# PCB_LineFollowerFullPCB.net
KiCad netlist of a schematic drawn in Altium Designer
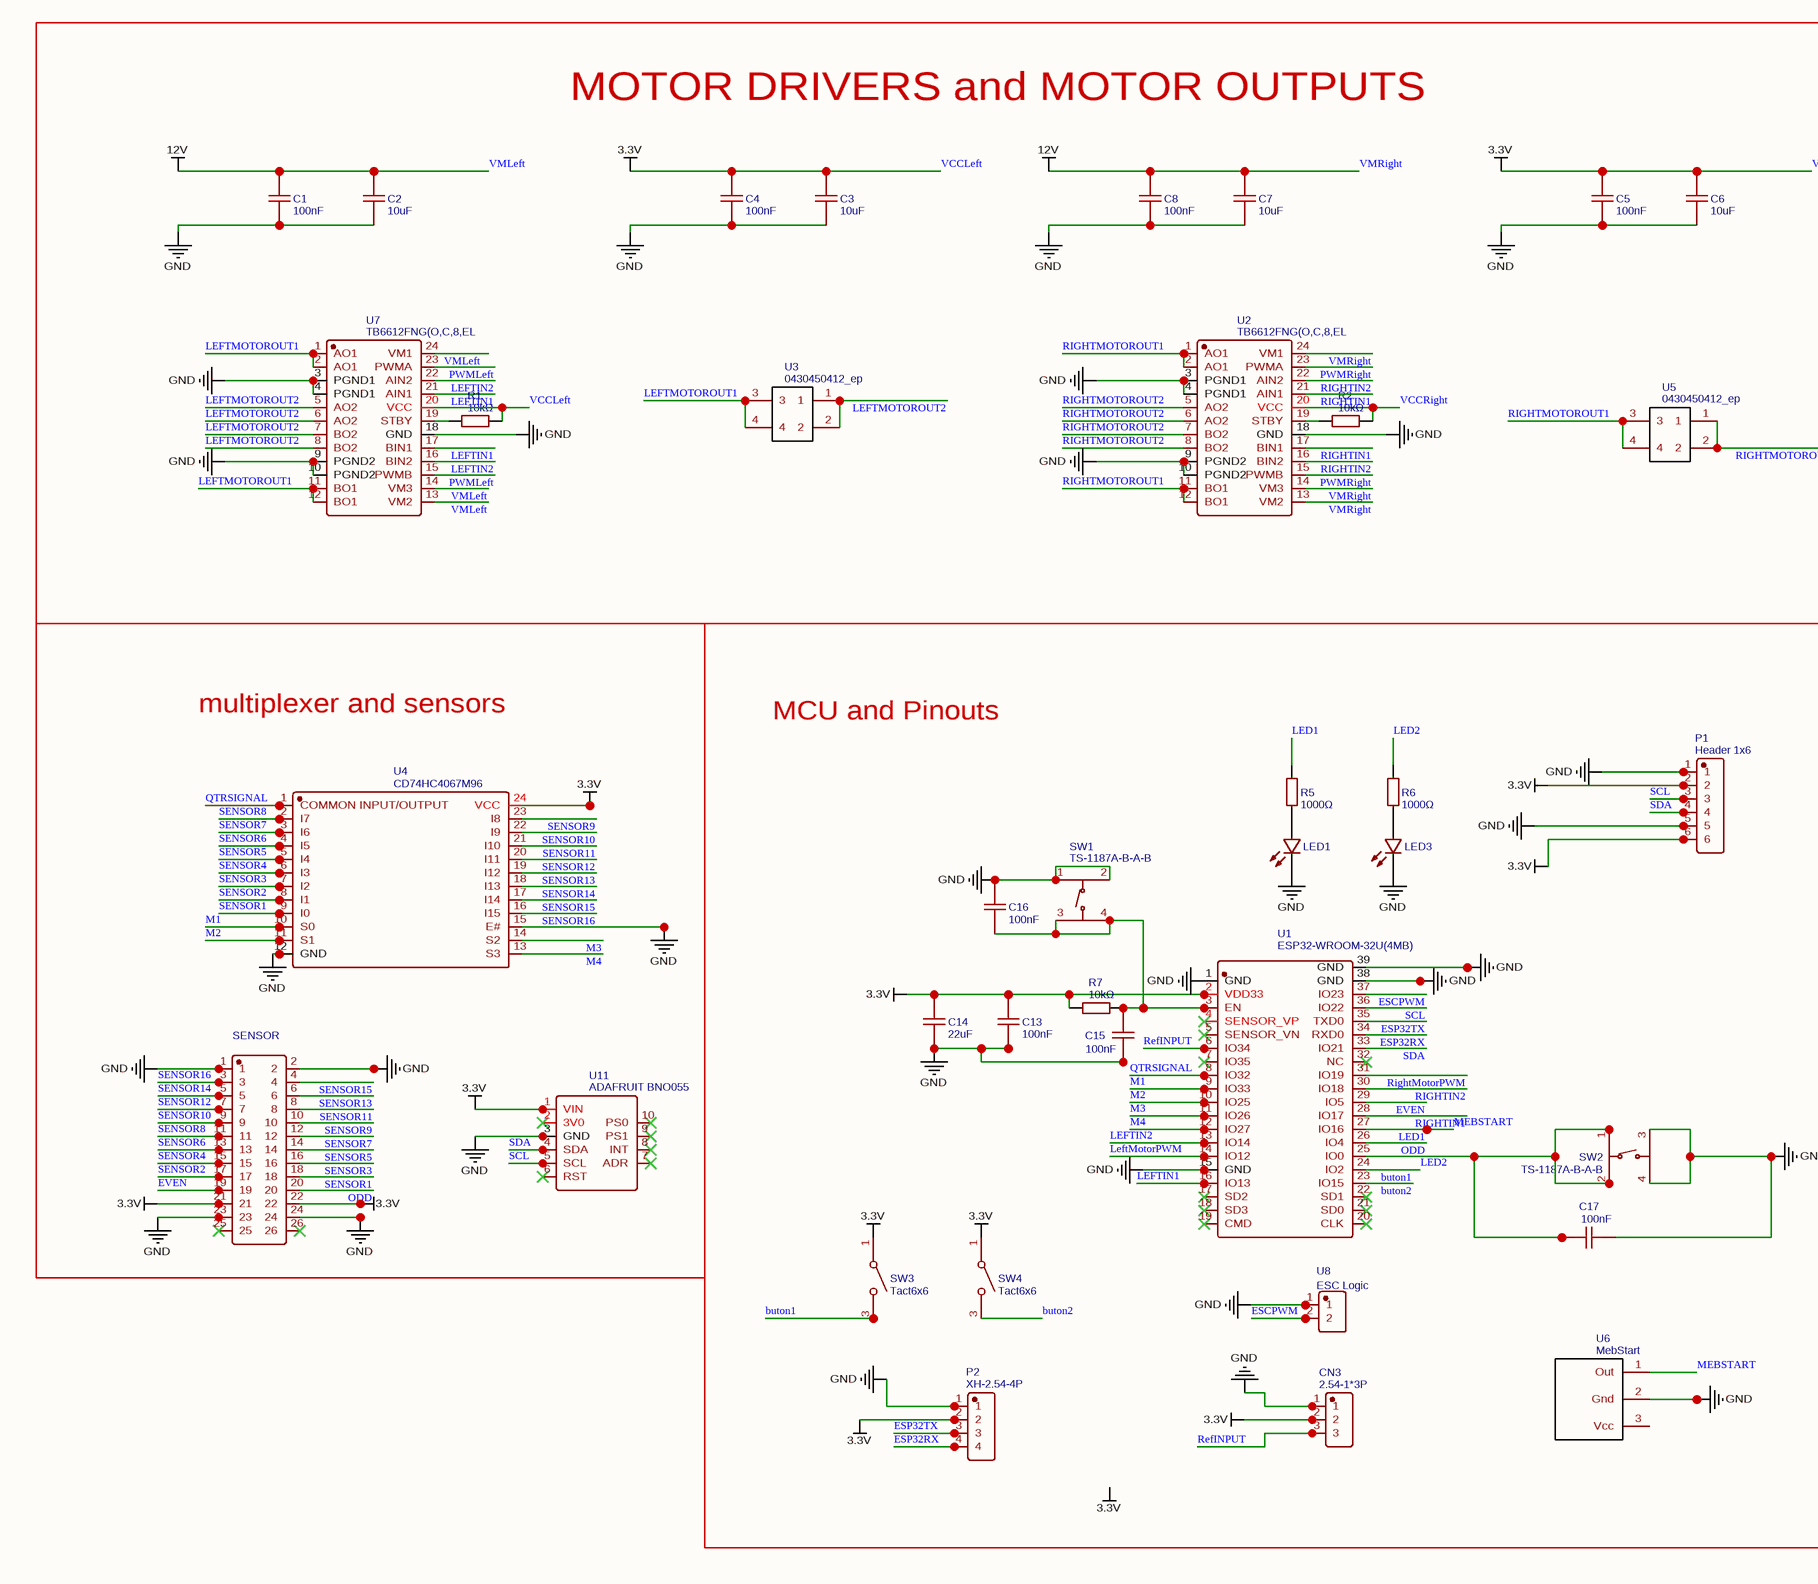
[diagram p0: PCB_LineFollowerFullPCB.schdoc, left]
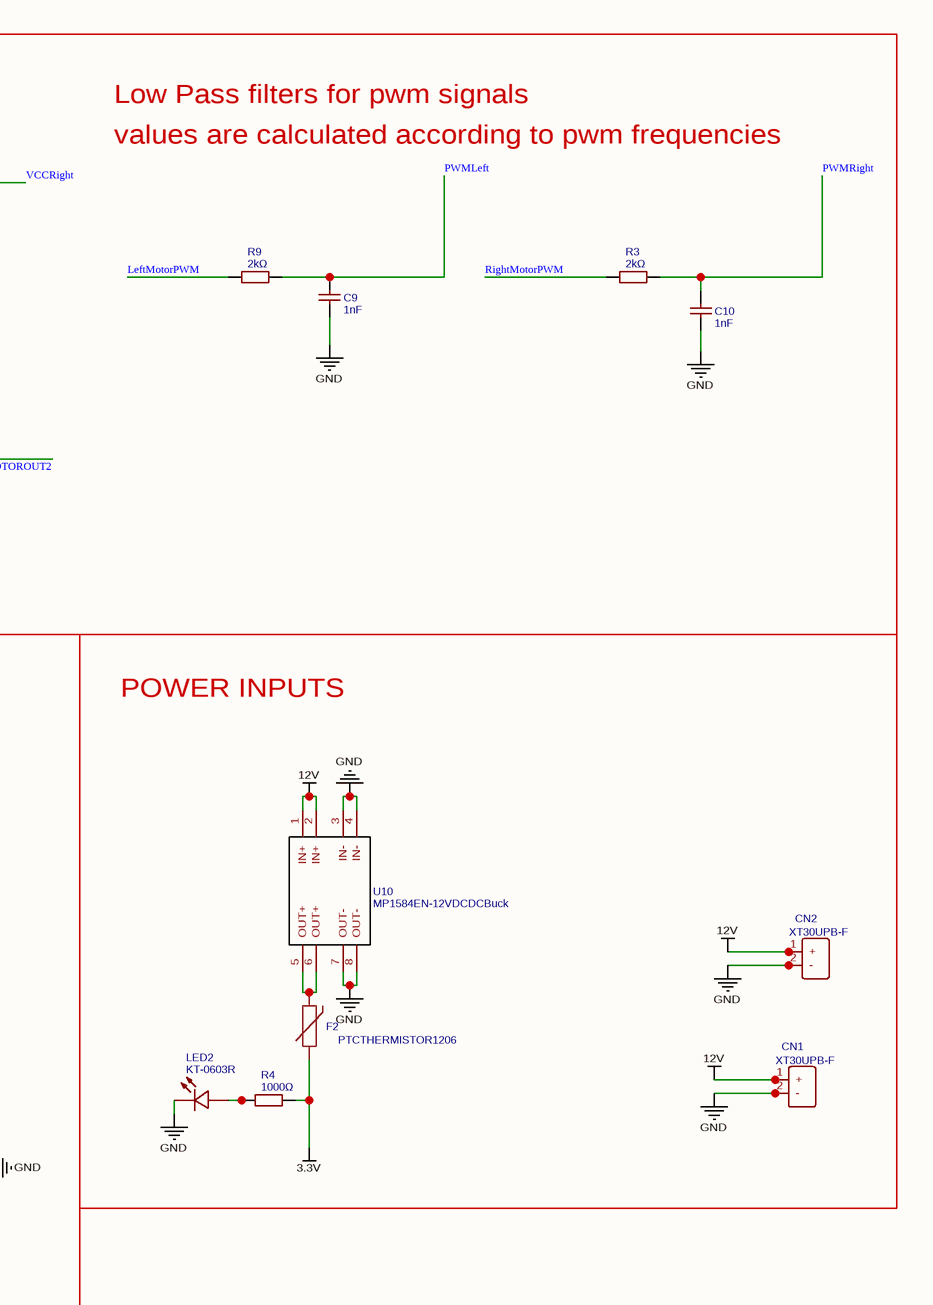
[diagram p1: PCB_LineFollowerFullPCB.schdoc, right]

(export (version "E")
  (design (tool "Eeschema 10.0.6"))
  (components
    (comp (ref "C1")
      (value "100nF")
      (fields
        (field (name "MANUFACTURER") "YAGEO(国巨)")
        (field (name "MANUFACTURER PART") "CC0603KRX7R9BB104")
      )
      (libsource (lib "altium-import") (part "root_3_100nF_"))
    )
    (comp (ref "C2")
      (value "10uF")
      (fields
        (field (name "MANUFACTURER") "SAMSUNG(三星)")
        (field (name "MANUFACTURER PART") "CL10A106MA8NRNC")
      )
      (libsource (lib "altium-import") (part "root_3_10uF_"))
    )
    (comp (ref "C3")
      (value "10uF")
      (fields
        (field (name "MANUFACTURER") "SAMSUNG(三星)")
        (field (name "MANUFACTURER PART") "CL10A106MA8NRNC")
      )
      (libsource (lib "altium-import") (part "root_3_10uF_"))
    )
    (comp (ref "C4")
      (value "100nF")
      (fields
        (field (name "MANUFACTURER") "YAGEO(国巨)")
        (field (name "MANUFACTURER PART") "CC0603KRX7R9BB104")
      )
      (libsource (lib "altium-import") (part "root_3_100nF_"))
    )
    (comp (ref "C5")
      (value "100nF")
      (fields
        (field (name "MANUFACTURER") "YAGEO(国巨)")
        (field (name "MANUFACTURER PART") "CC0603KRX7R9BB104")
      )
      (libsource (lib "altium-import") (part "root_3_100nF_"))
    )
    (comp (ref "C6")
      (value "10uF")
      (fields
        (field (name "MANUFACTURER") "SAMSUNG(三星)")
        (field (name "MANUFACTURER PART") "CL10A106MA8NRNC")
      )
      (libsource (lib "altium-import") (part "root_3_10uF_"))
    )
    (comp (ref "C7")
      (value "10uF")
      (fields
        (field (name "MANUFACTURER") "SAMSUNG(三星)")
        (field (name "MANUFACTURER PART") "CL10A106MA8NRNC")
      )
      (libsource (lib "altium-import") (part "root_3_10uF_"))
    )
    (comp (ref "C8")
      (value "100nF")
      (fields
        (field (name "MANUFACTURER") "YAGEO(国巨)")
        (field (name "MANUFACTURER PART") "CC0603KRX7R9BB104")
      )
      (libsource (lib "altium-import") (part "root_3_100nF_"))
    )
    (comp (ref "C9")
      (value "1nF")
      (fields
        (field (name "MANUFACTURER PART") "CL10B102KB8NNNC")
        (field (name "MANUFACTURER") "SAMSUNG(三星)")
      )
      (libsource (lib "altium-import") (part "root_3_1nF_"))
    )
    (comp (ref "C10")
      (value "1nF")
      (fields
        (field (name "MANUFACTURER PART") "CL10B102KB8NNNC")
        (field (name "MANUFACTURER") "SAMSUNG(三星)")
      )
      (libsource (lib "altium-import") (part "root_3_1nF_"))
    )
    (comp (ref "C13")
      (value "100nF")
      (fields
        (field (name "MANUFACTURER") "YAGEO(国巨)")
        (field (name "MANUFACTURER PART") "CC0603KRX7R9BB104")
      )
      (libsource (lib "altium-import") (part "root_3_100nF_"))
    )
    (comp (ref "C14")
      (value "22uF")
      (fields
        (field (name "MANUFACTURER") "SAMSUNG(三星)")
        (field (name "MANUFACTURER PART") "CL10A226MQ8NRNC")
      )
      (libsource (lib "altium-import") (part "root_1_22uF_"))
    )
    (comp (ref "C15")
      (value "100nF")
      (fields
        (field (name "MANUFACTURER") "YAGEO(国巨)")
        (field (name "MANUFACTURER PART") "CC0603KRX7R9BB104")
      )
      (libsource (lib "altium-import") (part "root_3_100nF_"))
    )
    (comp (ref "C16")
      (value "100nF")
      (fields
        (field (name "MANUFACTURER") "YAGEO(国巨)")
        (field (name "MANUFACTURER PART") "CC0603KRX7R9BB104")
      )
      (libsource (lib "altium-import") (part "root_3_100nF_"))
    )
    (comp (ref "C17")
      (value "100nF")
      (fields
        (field (name "MANUFACTURER") "YAGEO(国巨)")
        (field (name "MANUFACTURER PART") "CC0603KRX7R9BB104")
      )
      (libsource (lib "altium-import") (part "root_2_100nF_"))
    )
    (comp (ref "CN1")
      (value "XT30UPB-F")
      (fields
        (field (name "MANUFACTURER") "AMASS(艾迈斯)")
        (field (name "MANUFACTURER PART") "XT30UPB30-F.G.*")
        (field (name "CONTRIBUTOR") "LCSC")
      )
      (libsource (lib "altium-import") (part "root_0_XT30UPB-F_"))
    )
    (comp (ref "CN2")
      (value "XT30UPB-F")
      (fields
        (field (name "MANUFACTURER") "AMASS(艾迈斯)")
        (field (name "MANUFACTURER PART") "XT30UPB30-F.G.*")
        (field (name "CONTRIBUTOR") "LCSC")
      )
      (libsource (lib "altium-import") (part "root_0_XT30UPB-F_"))
    )
    (comp (ref "CN3")
      (value "2.54-1*3P")
      (fields (field (name "MANUFACTURER") "CAX(创都)") (field (name "CONTRIBUTOR") "LCSC"))
      (libsource (lib "altium-import") (part "root_0_2.54-1*3P_"))
    )
    (comp (ref "F2")
      (value "PTCTHERMISTOR1206")
      (description "Resettable Fuse PTC")
      (fields (field (name "CONTRIBUTOR") "varaksachin"))
      (libsource (lib "altium-import") (part "root_2_PTCTHERMISTOR1206_"))
    )
    (comp (ref "LED1")
      (value "19-217/BHC-ZL1M2RY/3T")
      (fields (field (name "MANUFACTURER") "EVERLIGHT(亿光)"))
      (libsource (lib "altium-import") (part "root_1_19-217/BHC-ZL1M2RY/3T_"))
    )
    (comp (ref "LED2")
      (value "KT-0603R")
      (fields (field (name "MANUFACTURER") "KENTO"))
      (libsource (lib "altium-import") (part "root_0_KT-0603R_"))
    )
    (comp (ref "LED3")
      (value "19-217/BHC-ZL1M2RY/3T")
      (fields (field (name "MANUFACTURER") "EVERLIGHT(亿光)"))
      (libsource (lib "altium-import") (part "root_1_19-217/BHC-ZL1M2RY/3T_"))
    )
    (comp (ref "P1")
      (value "Header 1x6")
      (fields
        (field (name "MANUFACTURER") "XFCN")
        (field (name "MANUFACTURER PART") "M3025V-1x6P")
        (field (name "CONTRIBUTOR") "erzyk")
      )
      (libsource (lib "altium-import") (part "root_0_Header 1x6_"))
    )
    (comp (ref "P2")
      (value "XH-2.54-4P")
      (fields (field (name "CONTRIBUTOR") "LCSC"))
      (libsource (lib "altium-import") (part "root_0_XH-2.54-4P_"))
    )
    (comp (ref "R1")
      (value "10kΩ")
      (fields
        (field (name "MANUFACTURER") "UNI-ROYAL(厚声)")
        (field (name "MANUFACTURER PART") "0603WAF1002T5E")
      )
      (libsource (lib "altium-import") (part "root_0_10kΩ_"))
    )
    (comp (ref "R2")
      (value "10kΩ")
      (fields
        (field (name "MANUFACTURER") "UNI-ROYAL(厚声)")
        (field (name "MANUFACTURER PART") "0603WAF1002T5E")
      )
      (libsource (lib "altium-import") (part "root_0_10kΩ_"))
    )
    (comp (ref "R3")
      (value "2kΩ")
      (fields
        (field (name "MANUFACTURER") "UNI-ROYAL(厚声)")
        (field (name "MANUFACTURER PART") "0603WAF2001T5E")
      )
      (libsource (lib "altium-import") (part "root_0_2kΩ_"))
    )
    (comp (ref "R4")
      (value "1000Ω")
      (fields
        (field (name "MANUFACTURER") "UNI-ROYAL(厚声)")
        (field (name "MANUFACTURER PART") "0603WAF1000T5E")
      )
      (libsource (lib "altium-import") (part "root_0_1000Ω_"))
    )
    (comp (ref "R5")
      (value "1000Ω")
      (fields
        (field (name "MANUFACTURER") "UNI-ROYAL(厚声)")
        (field (name "MANUFACTURER PART") "0603WAF510JT5E")
      )
      (libsource (lib "altium-import") (part "root_3_1000Ω_"))
    )
    (comp (ref "R6")
      (value "1000Ω")
      (fields
        (field (name "MANUFACTURER") "UNI-ROYAL(厚声)")
        (field (name "MANUFACTURER PART") "0603WAF510JT5E")
      )
      (libsource (lib "altium-import") (part "root_3_1000Ω_"))
    )
    (comp (ref "R7")
      (value "10kΩ")
      (fields
        (field (name "MANUFACTURER") "UNI-ROYAL(厚声)")
        (field (name "MANUFACTURER PART") "0603WAF1002T5E")
      )
      (libsource (lib "altium-import") (part "root_0_10kΩ_"))
    )
    (comp (ref "R9")
      (value "2kΩ")
      (fields
        (field (name "MANUFACTURER") "UNI-ROYAL(厚声)")
        (field (name "MANUFACTURER PART") "0603WAF2001T5E")
      )
      (libsource (lib "altium-import") (part "root_0_2kΩ_"))
    )
    (comp (ref "SENSOR")
      (value "X9555WV-2X13E-PTV01")
      (fields
        (field (name "MANUFACTURER") "XKB Connectivity(中国星坤)")
        (field (name "MANUFACTURER PART") "X9555WV-2x13E-PTV01")
        (field (name "CONTRIBUTOR") "LCSC")
      )
      (libsource (lib "altium-import") (part "root_0_X9555WV-2X13E-PTV01_"))
    )
    (comp (ref "SW1")
      (value "TS-1187A-B-A-B")
      (fields (field (name "MANUFACTURER") "XKB Connectivity(中国星坤)") (field (name "CONTRIBUTOR") "LCSC"))
      (libsource (lib "altium-import") (part "root_0_TS-1187A-B-A-B_"))
    )
    (comp (ref "SW2")
      (value "TS-1187A-B-A-B")
      (fields (field (name "MANUFACTURER") "XKB Connectivity(中国星坤)") (field (name "CONTRIBUTOR") "LCSC"))
      (libsource (lib "altium-import") (part "root_3_TS-1187A-B-A-B_"))
    )
    (comp (ref "SW3")
      (value "Tact6x6")
      (fields
        (field (name "MANUFACTURER") "BBJ")
        (field (name "MANUFACTURER PART") "Switch,6*6*6Plastic head,260G, 0.25mm,Straight line")
        (field (name "CONTRIBUTOR") "Richárd Tóth")
      )
      (libsource (lib "altium-import") (part "root_0_Tact6x6_"))
    )
    (comp (ref "SW4")
      (value "Tact6x6")
      (fields
        (field (name "MANUFACTURER") "BBJ")
        (field (name "MANUFACTURER PART") "Switch,6*6*6Plastic head,260G, 0.25mm,Straight line")
        (field (name "CONTRIBUTOR") "Richárd Tóth")
      )
      (libsource (lib "altium-import") (part "root_0_Tact6x6_"))
    )
    (comp (ref "U1")
      (value "ESP32-WROOM-32U(4MB)")
      (fields
        (field (name "MANUFACTURER") "ESPRESSIF(乐鑫)")
        (field (name "MANUFACTURER PART") "ESP32-WROOM-32U-N4")
        (field (name "CONTRIBUTOR") "LCSC")
      )
      (libsource (lib "altium-import") (part "root_0_ESP32-WROOM-32U(4MB)_"))
    )
    (comp (ref "U2")
      (value "TB6612FNG(O,C,8,EL")
      (fields (field (name "MANUFACTURER") "TOSHIBA(东芝)"))
      (libsource (lib "altium-import") (part "root_0_TB6612FNG(O,C,8,EL_"))
    )
    (comp (ref "U3")
      (value "0430450412_ep")
      (fields (field (name "CONTRIBUTOR") "epsilor"))
      (libsource (lib "altium-import") (part "root_0_0430450412_ep_"))
    )
    (comp (ref "U4")
      (value "CD74HC4067M96")
      (fields (field (name "MANUFACTURER") "TI(德州仪器)") (field (name "CONTRIBUTOR") "LCSC"))
      (libsource (lib "altium-import") (part "root_0_CD74HC4067M96_"))
    )
    (comp (ref "U5")
      (value "0430450412_ep")
      (fields (field (name "CONTRIBUTOR") "epsilor"))
      (libsource (lib "altium-import") (part "root_0_0430450412_ep_"))
    )
    (comp (ref "U6")
      (value "MebStart")
      (fields (field (name "CONTRIBUTOR") "cikkan"))
      (libsource (lib "altium-import") (part "root_0_MebStart_"))
    )
    (comp (ref "U7")
      (value "TB6612FNG(O,C,8,EL")
      (fields (field (name "MANUFACTURER") "TOSHIBA(东芝)"))
      (libsource (lib "altium-import") (part "root_0_TB6612FNG(O,C,8,EL_"))
    )
    (comp (ref "U8")
      (value "ESC Logic")
      (fields (field (name "MANUFACTURER PART") "XH-2P-2.54") (field (name "CONTRIBUTOR") "LCSC"))
      (libsource (lib "altium-import") (part "root_0_ESC Logic_"))
    )
    (comp (ref "U10")
      (value "MP1584EN-12VDCDCBuck")
      (fields
        (field (name "MANUFACTURER") "eBoot")
        (field (name "MANUFACTURER PART") "MP1584EN")
        (field (name "CONTRIBUTOR") "pep9571")
      )
      (libsource (lib "altium-import") (part "root_0_MP1584EN-12VDCDCBuck_"))
    )
    (comp (ref "U11")
      (value "ADAFRUIT BNO055")
      (fields (field (name "CONTRIBUTOR") "andreastryph"))
      (libsource (lib "altium-import") (part "root_0_ADAFRUIT BNO055_"))
    )
  )
  (nets
    (net (code "1") (name "/ESCPWM") (class "Default")
      (node (ref "U1") (pin "37") (pinfunction "IO23_37") (pintype "passive"))
      (node (ref "U8") (pin "2") (pinfunction "2_2") (pintype "passive"))
    )
    (net (code "2") (name "/ESP32RX") (class "Default")
      (node (ref "P2") (pin "4") (pinfunction "4_4") (pintype "passive"))
      (node (ref "U1") (pin "34") (pinfunction "RXD0_34") (pintype "passive"))
    )
    (net (code "3") (name "/ESP32TX") (class "Default")
      (node (ref "P2") (pin "3") (pinfunction "3_3") (pintype "passive"))
      (node (ref "U1") (pin "35") (pinfunction "TXD0_35") (pintype "passive"))
    )
    (net (code "4") (name "/EVEN") (class "Default")
      (node (ref "SENSOR") (pin "19") (pinfunction "19_19") (pintype "passive"))
      (node (ref "U1") (pin "29") (pinfunction "IO5_29") (pintype "passive"))
    )
    (net (code "5") (name "/LED1") (class "Default")
      (node (ref "R5") (pin "1") (pinfunction "1_1") (pintype "passive"))
      (node (ref "U1") (pin "27") (pinfunction "IO16_27") (pintype "passive"))
      (node (ref "U6") (pin "1") (pinfunction "Out_1") (pintype "passive"))
    )
    (net (code "6") (name "/LED2") (class "Default")
      (node (ref "R6") (pin "1") (pinfunction "1_1") (pintype "passive"))
      (node (ref "SW3") (pin "3") (pinfunction "2_3") (pintype "passive"))
      (node (ref "U1") (pin "24") (pinfunction "IO2_24") (pintype "passive"))
    )
    (net (code "7") (name "/LEFTIN1") (class "Default")
      (node (ref "U1") (pin "16") (pinfunction "IO13_16") (pintype "passive"))
      (node (ref "U7") (pin "17") (pinfunction "BIN1_17") (pintype "passive"))
      (node (ref "U7") (pin "21") (pinfunction "AIN1_21") (pintype "passive"))
    )
    (net (code "8") (name "/LEFTIN2") (class "Default")
      (node (ref "U1") (pin "13") (pinfunction "IO14_13") (pintype "passive"))
      (node (ref "U7") (pin "16") (pinfunction "BIN2_16") (pintype "passive"))
      (node (ref "U7") (pin "22") (pinfunction "AIN2_22") (pintype "passive"))
    )
    (net (code "9") (name "/LEFTMOTOROUT1") (class "Default")
      (node (ref "U3") (pin "3") (pinfunction "3_3") (pintype "passive"))
      (node (ref "U3") (pin "4") (pinfunction "4_4") (pintype "passive"))
      (node (ref "U7") (pin "1") (pinfunction "AO1_1") (pintype "passive"))
      (node (ref "U7") (pin "11") (pinfunction "BO1_11") (pintype "passive"))
      (node (ref "U7") (pin "12") (pinfunction "BO1_12") (pintype "passive"))
      (node (ref "U7") (pin "2") (pinfunction "AO1_2") (pintype "passive"))
    )
    (net (code "10") (name "/LEFTMOTOROUT2") (class "Default")
      (node (ref "U3") (pin "1") (pinfunction "1_1") (pintype "passive"))
      (node (ref "U3") (pin "2") (pinfunction "2_2") (pintype "passive"))
      (node (ref "U7") (pin "5") (pinfunction "AO2_5") (pintype "passive"))
      (node (ref "U7") (pin "6") (pinfunction "AO2_6") (pintype "passive"))
      (node (ref "U7") (pin "7") (pinfunction "BO2_7") (pintype "passive"))
      (node (ref "U7") (pin "8") (pinfunction "BO2_8") (pintype "passive"))
    )
    (net (code "11") (name "/LeftMotorPWM") (class "Default")
      (node (ref "R9") (pin "1") (pinfunction "1_1") (pintype "passive"))
      (node (ref "U1") (pin "14") (pinfunction "IO12_14") (pintype "passive"))
    )
    (net (code "12") (name "/M1") (class "Default")
      (node (ref "U1") (pin "9") (pinfunction "IO33_9") (pintype "passive"))
      (node (ref "U4") (pin "10") (pinfunction "S0_10") (pintype "passive"))
    )
    (net (code "13") (name "/M2") (class "Default")
      (node (ref "U1") (pin "10") (pinfunction "IO25_10") (pintype "passive"))
      (node (ref "U4") (pin "11") (pinfunction "S1_11") (pintype "passive"))
    )
    (net (code "14") (name "/M3") (class "Default")
      (node (ref "U1") (pin "11") (pinfunction "IO26_11") (pintype "passive"))
      (node (ref "U4") (pin "14") (pinfunction "S2_14") (pintype "passive"))
    )
    (net (code "15") (name "/M4") (class "Default")
      (node (ref "U1") (pin "12") (pinfunction "IO27_12") (pintype "passive"))
      (node (ref "U4") (pin "13") (pinfunction "S3_13") (pintype "passive"))
    )
    (net (code "16") (name "/ODD") (class "Default")
      (node (ref "SENSOR") (pin "20") (pinfunction "20_20") (pintype "passive"))
      (node (ref "U1") (pin "26") (pinfunction "IO4_26") (pintype "passive"))
    )
    (net (code "17") (name "/PWMLeft") (class "Default")
      (node (ref "C9") (pin "1") (pinfunction "1_1") (pintype "passive"))
      (node (ref "R9") (pin "2") (pinfunction "2_2") (pintype "passive"))
      (node (ref "U7") (pin "15") (pinfunction "PWMB_15") (pintype "passive"))
      (node (ref "U7") (pin "23") (pinfunction "PWMA_23") (pintype "passive"))
    )
    (net (code "18") (name "/PWMRight") (class "Default")
      (node (ref "C10") (pin "1") (pinfunction "1_1") (pintype "passive"))
      (node (ref "R3") (pin "2") (pinfunction "2_2") (pintype "passive"))
      (node (ref "U2") (pin "15") (pinfunction "PWMB_15") (pintype "passive"))
      (node (ref "U2") (pin "23") (pinfunction "PWMA_23") (pintype "passive"))
    )
    (net (code "19") (name "/QTRSIGNAL") (class "Default")
      (node (ref "U1") (pin "8") (pinfunction "IO32_8") (pintype "passive"))
      (node (ref "U4") (pin "1") (pinfunction "COMMON_INPUT/OUTPUT_1") (pintype "passive"))
    )
    (net (code "20") (name "/RIGHTIN1") (class "Default")
      (node (ref "U1") (pin "28") (pinfunction "IO17_28") (pintype "passive"))
      (node (ref "U2") (pin "17") (pinfunction "BIN1_17") (pintype "passive"))
      (node (ref "U2") (pin "21") (pinfunction "AIN1_21") (pintype "passive"))
    )
    (net (code "21") (name "/RIGHTIN2") (class "Default")
      (node (ref "U1") (pin "30") (pinfunction "IO18_30") (pintype "passive"))
      (node (ref "U2") (pin "16") (pinfunction "BIN2_16") (pintype "passive"))
      (node (ref "U2") (pin "22") (pinfunction "AIN2_22") (pintype "passive"))
    )
    (net (code "22") (name "/RIGHTMOTOROUT1") (class "Default")
      (node (ref "U2") (pin "1") (pinfunction "AO1_1") (pintype "passive"))
      (node (ref "U2") (pin "11") (pinfunction "BO1_11") (pintype "passive"))
      (node (ref "U2") (pin "12") (pinfunction "BO1_12") (pintype "passive"))
      (node (ref "U2") (pin "2") (pinfunction "AO1_2") (pintype "passive"))
      (node (ref "U5") (pin "3") (pinfunction "3_3") (pintype "passive"))
      (node (ref "U5") (pin "4") (pinfunction "4_4") (pintype "passive"))
    )
    (net (code "23") (name "/RIGHTMOTOROUT2") (class "Default")
      (node (ref "U2") (pin "5") (pinfunction "AO2_5") (pintype "passive"))
      (node (ref "U2") (pin "6") (pinfunction "AO2_6") (pintype "passive"))
      (node (ref "U2") (pin "7") (pinfunction "BO2_7") (pintype "passive"))
      (node (ref "U2") (pin "8") (pinfunction "BO2_8") (pintype "passive"))
      (node (ref "U5") (pin "1") (pinfunction "1_1") (pintype "passive"))
      (node (ref "U5") (pin "2") (pinfunction "2_2") (pintype "passive"))
    )
    (net (code "24") (name "/RefINPUT") (class "Default")
      (node (ref "CN3") (pin "3") (pinfunction "3_3") (pintype "passive"))
      (node (ref "U1") (pin "6") (pinfunction "IO34_6") (pintype "passive"))
    )
    (net (code "25") (name "/RightMotorPWM") (class "Default")
      (node (ref "R3") (pin "1") (pinfunction "1_1") (pintype "passive"))
      (node (ref "U1") (pin "31") (pinfunction "IO19_31") (pintype "passive"))
    )
    (net (code "26") (name "/SCL") (class "Default")
      (node (ref "P1") (pin "3") (pinfunction "3_3") (pintype "passive"))
      (node (ref "U1") (pin "36") (pinfunction "IO22_36") (pintype "passive"))
      (node (ref "U11") (pin "5") (pinfunction "SCL_5") (pintype "passive"))
    )
    (net (code "27") (name "/SDA") (class "Default")
      (node (ref "P1") (pin "4") (pinfunction "4_4") (pintype "passive"))
      (node (ref "U1") (pin "33") (pinfunction "IO21_33") (pintype "passive"))
      (node (ref "U11") (pin "4") (pinfunction "SDA_4") (pintype "passive"))
    )
    (net (code "28") (name "/SENSOR1") (class "Default")
      (node (ref "SENSOR") (pin "18") (pinfunction "18_18") (pintype "passive"))
      (node (ref "U4") (pin "9") (pinfunction "I0_9") (pintype "passive"))
    )
    (net (code "29") (name "/SENSOR2") (class "Default")
      (node (ref "SENSOR") (pin "17") (pinfunction "17_17") (pintype "passive"))
      (node (ref "U4") (pin "8") (pinfunction "I1_8") (pintype "passive"))
    )
    (net (code "30") (name "/SENSOR3") (class "Default")
      (node (ref "SENSOR") (pin "16") (pinfunction "16_16") (pintype "passive"))
      (node (ref "U4") (pin "7") (pinfunction "I2_7") (pintype "passive"))
    )
    (net (code "31") (name "/SENSOR4") (class "Default")
      (node (ref "SENSOR") (pin "15") (pinfunction "15_15") (pintype "passive"))
      (node (ref "U4") (pin "6") (pinfunction "I3_6") (pintype "passive"))
    )
    (net (code "32") (name "/SENSOR5") (class "Default")
      (node (ref "SENSOR") (pin "14") (pinfunction "14_14") (pintype "passive"))
      (node (ref "U4") (pin "5") (pinfunction "I4_5") (pintype "passive"))
    )
    (net (code "33") (name "/SENSOR6") (class "Default")
      (node (ref "SENSOR") (pin "13") (pinfunction "13_13") (pintype "passive"))
      (node (ref "U4") (pin "4") (pinfunction "I5_4") (pintype "passive"))
    )
    (net (code "34") (name "/SENSOR7") (class "Default")
      (node (ref "SENSOR") (pin "12") (pinfunction "12_12") (pintype "passive"))
      (node (ref "U4") (pin "3") (pinfunction "I6_3") (pintype "passive"))
    )
    (net (code "35") (name "/SENSOR8") (class "Default")
      (node (ref "SENSOR") (pin "11") (pinfunction "11_11") (pintype "passive"))
      (node (ref "U4") (pin "2") (pinfunction "I7_2") (pintype "passive"))
    )
    (net (code "36") (name "/SENSOR9") (class "Default")
      (node (ref "SENSOR") (pin "10") (pinfunction "10_10") (pintype "passive"))
      (node (ref "U4") (pin "23") (pinfunction "I8_23") (pintype "passive"))
    )
    (net (code "37") (name "/SENSOR10") (class "Default")
      (node (ref "SENSOR") (pin "9") (pinfunction "9_9") (pintype "passive"))
      (node (ref "U4") (pin "22") (pinfunction "I9_22") (pintype "passive"))
    )
    (net (code "38") (name "/SENSOR11") (class "Default")
      (node (ref "SENSOR") (pin "8") (pinfunction "8_8") (pintype "passive"))
      (node (ref "U4") (pin "21") (pinfunction "I10_21") (pintype "passive"))
    )
    (net (code "39") (name "/SENSOR12") (class "Default")
      (node (ref "SENSOR") (pin "7") (pinfunction "7_7") (pintype "passive"))
      (node (ref "U4") (pin "20") (pinfunction "I11_20") (pintype "passive"))
    )
    (net (code "40") (name "/SENSOR13") (class "Default")
      (node (ref "SENSOR") (pin "6") (pinfunction "6_6") (pintype "passive"))
      (node (ref "U4") (pin "19") (pinfunction "I12_19") (pintype "passive"))
    )
    (net (code "41") (name "/SENSOR14") (class "Default")
      (node (ref "SENSOR") (pin "5") (pinfunction "5_5") (pintype "passive"))
      (node (ref "U4") (pin "18") (pinfunction "I13_18") (pintype "passive"))
    )
    (net (code "42") (name "/SENSOR15") (class "Default")
      (node (ref "SENSOR") (pin "4") (pinfunction "4_4") (pintype "passive"))
      (node (ref "U4") (pin "17") (pinfunction "I14_17") (pintype "passive"))
    )
    (net (code "43") (name "/SENSOR16") (class "Default")
      (node (ref "SENSOR") (pin "3") (pinfunction "3_3") (pintype "passive"))
      (node (ref "U4") (pin "16") (pinfunction "I15_16") (pintype "passive"))
    )
    (net (code "44") (name "/buton2") (class "Default")
      (node (ref "SW4") (pin "3") (pinfunction "2_3") (pintype "passive"))
      (node (ref "U1") (pin "23") (pinfunction "IO15_23") (pintype "passive"))
    )
    (net (code "45") (name "3.3V") (class "Default")
      (node (ref "C13") (pin "1") (pinfunction "1_1") (pintype "passive"))
      (node (ref "C14") (pin "2") (pinfunction "2_2") (pintype "passive"))
      (node (ref "C3") (pin "1") (pinfunction "1_1") (pintype "passive"))
      (node (ref "C4") (pin "1") (pinfunction "1_1") (pintype "passive"))
      (node (ref "C5") (pin "1") (pinfunction "1_1") (pintype "passive"))
      (node (ref "C6") (pin "1") (pinfunction "1_1") (pintype "passive"))
      (node (ref "CN3") (pin "2") (pinfunction "2_2") (pintype "passive"))
      (node (ref "F2") (pin "1") (pinfunction "1_1") (pintype "passive"))
      (node (ref "P1") (pin "2") (pinfunction "2_2") (pintype "passive"))
      (node (ref "P1") (pin "6") (pinfunction "6_6") (pintype "passive"))
      (node (ref "P2") (pin "2") (pinfunction "2_2") (pintype "passive"))
      (node (ref "R1") (pin "2") (pinfunction "2_2") (pintype "passive"))
      (node (ref "R2") (pin "2") (pinfunction "2_2") (pintype "passive"))
      (node (ref "R4") (pin "2") (pinfunction "2_2") (pintype "passive"))
      (node (ref "R7") (pin "1") (pinfunction "1_1") (pintype "passive"))
      (node (ref "SENSOR") (pin "21") (pinfunction "21_21") (pintype "passive"))
      (node (ref "SENSOR") (pin "22") (pinfunction "22_22") (pintype "passive"))
      (node (ref "SW3") (pin "1") (pinfunction "1_1") (pintype "passive"))
      (node (ref "SW4") (pin "1") (pinfunction "1_1") (pintype "passive"))
      (node (ref "U1") (pin "2") (pinfunction "VDD33_2") (pintype "passive"))
      (node (ref "U11") (pin "1") (pinfunction "VIN_1") (pintype "passive"))
      (node (ref "U2") (pin "20") (pinfunction "VCC_20") (pintype "passive"))
      (node (ref "U4") (pin "24") (pinfunction "VCC_24") (pintype "passive"))
      (node (ref "U7") (pin "20") (pinfunction "VCC_20") (pintype "passive"))
    )
    (net (code "46") (name "12V") (class "Default")
      (node (ref "C1") (pin "1") (pinfunction "1_1") (pintype "passive"))
      (node (ref "C2") (pin "1") (pinfunction "1_1") (pintype "passive"))
      (node (ref "C7") (pin "1") (pinfunction "1_1") (pintype "passive"))
      (node (ref "C8") (pin "1") (pinfunction "1_1") (pintype "passive"))
      (node (ref "CN1") (pin "1") (pinfunction "+_1") (pintype "passive"))
      (node (ref "CN2") (pin "1") (pinfunction "+_1") (pintype "passive"))
      (node (ref "U10") (pin "1") (pinfunction "IN+_1") (pintype "passive"))
      (node (ref "U10") (pin "2") (pinfunction "IN+_2") (pintype "passive"))
      (node (ref "U2") (pin "13") (pinfunction "VM2_13") (pintype "passive"))
      (node (ref "U2") (pin "14") (pinfunction "VM3_14") (pintype "passive"))
      (node (ref "U2") (pin "24") (pinfunction "VM1_24") (pintype "passive"))
      (node (ref "U7") (pin "13") (pinfunction "VM2_13") (pintype "passive"))
      (node (ref "U7") (pin "14") (pinfunction "VM3_14") (pintype "passive"))
      (node (ref "U7") (pin "24") (pinfunction "VM1_24") (pintype "passive"))
    )
    (net (code "47") (name "GND") (class "Default")
      (node (ref "C1") (pin "2") (pinfunction "2_2") (pintype "passive"))
      (node (ref "C10") (pin "2") (pinfunction "2_2") (pintype "passive"))
      (node (ref "C13") (pin "2") (pinfunction "2_2") (pintype "passive"))
      (node (ref "C14") (pin "1") (pinfunction "1_1") (pintype "passive"))
      (node (ref "C15") (pin "2") (pinfunction "2_2") (pintype "passive"))
      (node (ref "C16") (pin "1") (pinfunction "1_1") (pintype "passive"))
      (node (ref "C17") (pin "2") (pinfunction "2_2") (pintype "passive"))
      (node (ref "C2") (pin "2") (pinfunction "2_2") (pintype "passive"))
      (node (ref "C3") (pin "2") (pinfunction "2_2") (pintype "passive"))
      (node (ref "C4") (pin "2") (pinfunction "2_2") (pintype "passive"))
      (node (ref "C5") (pin "2") (pinfunction "2_2") (pintype "passive"))
      (node (ref "C6") (pin "2") (pinfunction "2_2") (pintype "passive"))
      (node (ref "C7") (pin "2") (pinfunction "2_2") (pintype "passive"))
      (node (ref "C8") (pin "2") (pinfunction "2_2") (pintype "passive"))
      (node (ref "C9") (pin "2") (pinfunction "2_2") (pintype "passive"))
      (node (ref "CN1") (pin "2") (pinfunction "-_2") (pintype "passive"))
      (node (ref "CN2") (pin "2") (pinfunction "-_2") (pintype "passive"))
      (node (ref "CN3") (pin "1") (pinfunction "1_1") (pintype "passive"))
      (node (ref "LED1") (pin "1") (pinfunction "C_1") (pintype "passive"))
      (node (ref "LED2") (pin "1") (pinfunction "K_1") (pintype "passive"))
      (node (ref "LED3") (pin "1") (pinfunction "C_1") (pintype "passive"))
      (node (ref "P1") (pin "1") (pinfunction "1_1") (pintype "passive"))
      (node (ref "P1") (pin "5") (pinfunction "5_5") (pintype "passive"))
      (node (ref "P2") (pin "1") (pinfunction "1_1") (pintype "passive"))
      (node (ref "SENSOR") (pin "1") (pinfunction "1_1") (pintype "passive"))
      (node (ref "SENSOR") (pin "2") (pinfunction "2_2") (pintype "passive"))
      (node (ref "SENSOR") (pin "23") (pinfunction "23_23") (pintype "passive"))
      (node (ref "SENSOR") (pin "24") (pinfunction "24_24") (pintype "passive"))
      (node (ref "SW1") (pin "1") (pinfunction "A_1") (pintype "passive"))
      (node (ref "SW1") (pin "2") (pinfunction "B_2") (pintype "passive"))
      (node (ref "SW2") (pin "3") (pinfunction "C_3") (pintype "passive"))
      (node (ref "SW2") (pin "4") (pinfunction "D_4") (pintype "passive"))
      (node (ref "U1") (pin "1") (pinfunction "GND_1") (pintype "passive"))
      (node (ref "U1") (pin "15") (pinfunction "GND_15") (pintype "passive"))
      (node (ref "U1") (pin "38") (pinfunction "GND_38") (pintype "passive"))
      (node (ref "U1") (pin "39") (pinfunction "GND_39") (pintype "passive"))
      (node (ref "U10") (pin "3") (pinfunction "IN-_3") (pintype "passive"))
      (node (ref "U10") (pin "4") (pinfunction "IN-_4") (pintype "passive"))
      (node (ref "U10") (pin "7") (pinfunction "OUT-_7") (pintype "passive"))
      (node (ref "U10") (pin "8") (pinfunction "OUT-_8") (pintype "passive"))
      (node (ref "U11") (pin "3") (pinfunction "GND_3") (pintype "passive"))
      (node (ref "U2") (pin "10") (pinfunction "PGND2_10") (pintype "passive"))
      (node (ref "U2") (pin "18") (pinfunction "GND_18") (pintype "passive"))
      (node (ref "U2") (pin "3") (pinfunction "PGND1_3") (pintype "passive"))
      (node (ref "U2") (pin "4") (pinfunction "PGND1_4") (pintype "passive"))
      (node (ref "U2") (pin "9") (pinfunction "PGND2_9") (pintype "passive"))
      (node (ref "U4") (pin "12") (pinfunction "GND_12") (pintype "passive"))
      (node (ref "U4") (pin "15") (pinfunction "E#_15") (pintype "passive"))
      (node (ref "U6") (pin "2") (pinfunction "Gnd_2") (pintype "passive"))
      (node (ref "U7") (pin "10") (pinfunction "PGND2_10") (pintype "passive"))
      (node (ref "U7") (pin "18") (pinfunction "GND_18") (pintype "passive"))
      (node (ref "U7") (pin "3") (pinfunction "PGND1_3") (pintype "passive"))
      (node (ref "U7") (pin "4") (pinfunction "PGND1_4") (pintype "passive"))
      (node (ref "U7") (pin "9") (pinfunction "PGND2_9") (pintype "passive"))
      (node (ref "U8") (pin "1") (pinfunction "1_1") (pintype "passive"))
    )
    (net (code "48") (name "Net-(F2-Pad2)") (class "Default")
      (node (ref "F2") (pin "2") (pinfunction "2_2") (pintype "passive"))
      (node (ref "U10") (pin "5") (pinfunction "OUT+_5") (pintype "passive"))
      (node (ref "U10") (pin "6") (pinfunction "OUT+_6") (pintype "passive"))
    )
    (net (code "49") (name "Net-(LED1-A)") (class "Default")
      (node (ref "LED1") (pin "2") (pinfunction "A_2") (pintype "passive"))
      (node (ref "R5") (pin "2") (pinfunction "2_2") (pintype "passive"))
    )
    (net (code "50") (name "Net-(LED2-A)") (class "Default")
      (node (ref "LED2") (pin "2") (pinfunction "A_2") (pintype "passive"))
      (node (ref "R4") (pin "1") (pinfunction "1_1") (pintype "passive"))
    )
    (net (code "51") (name "Net-(LED3-A)") (class "Default")
      (node (ref "LED3") (pin "2") (pinfunction "A_2") (pintype "passive"))
      (node (ref "R6") (pin "2") (pinfunction "2_2") (pintype "passive"))
    )
    (net (code "52") (name "Net-(SW1-C)") (class "Default")
      (node (ref "C15") (pin "1") (pinfunction "1_1") (pintype "passive"))
      (node (ref "C16") (pin "2") (pinfunction "2_2") (pintype "passive"))
      (node (ref "R7") (pin "2") (pinfunction "2_2") (pintype "passive"))
      (node (ref "SW1") (pin "3") (pinfunction "C_3") (pintype "passive"))
      (node (ref "SW1") (pin "4") (pinfunction "D_4") (pintype "passive"))
      (node (ref "U1") (pin "3") (pinfunction "EN_3") (pintype "passive"))
    )
    (net (code "53") (name "Net-(SW2-A)") (class "Default")
      (node (ref "C17") (pin "1") (pinfunction "1_1") (pintype "passive"))
      (node (ref "SW2") (pin "1") (pinfunction "A_1") (pintype "passive"))
      (node (ref "SW2") (pin "2") (pinfunction "B_2") (pintype "passive"))
      (node (ref "U1") (pin "25") (pinfunction "IO0_25") (pintype "passive"))
    )
    (net (code "54") (name "Net-(U2-STBY)") (class "Default")
      (node (ref "R2") (pin "1") (pinfunction "1_1") (pintype "passive"))
      (node (ref "U2") (pin "19") (pinfunction "STBY_19") (pintype "passive"))
    )
    (net (code "55") (name "Net-(U7-STBY)") (class "Default")
      (node (ref "R1") (pin "1") (pinfunction "1_1") (pintype "passive"))
      (node (ref "U7") (pin "19") (pinfunction "STBY_19") (pintype "passive"))
    )
    (net (code "56") (name "unconnected-(SENSOR-Pad25)") (class "Default")
      (node (ref "SENSOR") (pin "25") (pinfunction "25_25") (pintype "passive+no_connect"))
    )
    (net (code "57") (name "unconnected-(SENSOR-Pad26)") (class "Default")
      (node (ref "SENSOR") (pin "26") (pinfunction "26_26") (pintype "passive+no_connect"))
    )
    (net (code "58") (name "unconnected-(U1-CLK-Pad20)") (class "Default")
      (node (ref "U1") (pin "20") (pinfunction "CLK_20") (pintype "passive+no_connect"))
    )
    (net (code "59") (name "unconnected-(U1-CMD-Pad19)") (class "Default")
      (node (ref "U1") (pin "19") (pinfunction "CMD_19") (pintype "passive+no_connect"))
    )
    (net (code "60") (name "unconnected-(U1-IO35-Pad7)") (class "Default")
      (node (ref "U1") (pin "7") (pinfunction "IO35_7") (pintype "passive+no_connect"))
    )
    (net (code "61") (name "unconnected-(U1-NC-Pad32)") (class "Default")
      (node (ref "U1") (pin "32") (pinfunction "NC_32") (pintype "passive+no_connect"))
    )
    (net (code "62") (name "unconnected-(U1-SD0-Pad21)") (class "Default")
      (node (ref "U1") (pin "21") (pinfunction "SD0_21") (pintype "passive+no_connect"))
    )
    (net (code "63") (name "unconnected-(U1-SD1-Pad22)") (class "Default")
      (node (ref "U1") (pin "22") (pinfunction "SD1_22") (pintype "passive+no_connect"))
    )
    (net (code "64") (name "unconnected-(U1-SD2-Pad17)") (class "Default")
      (node (ref "U1") (pin "17") (pinfunction "SD2_17") (pintype "passive+no_connect"))
    )
    (net (code "65") (name "unconnected-(U1-SD3-Pad18)") (class "Default")
      (node (ref "U1") (pin "18") (pinfunction "SD3_18") (pintype "passive+no_connect"))
    )
    (net (code "66") (name "unconnected-(U1-SENSOR_VN-Pad5)") (class "Default")
      (node (ref "U1") (pin "5") (pinfunction "SENSOR_VN_5") (pintype "passive+no_connect"))
    )
    (net (code "67") (name "unconnected-(U1-SENSOR_VP-Pad4)") (class "Default")
      (node (ref "U1") (pin "4") (pinfunction "SENSOR_VP_4") (pintype "passive+no_connect"))
    )
    (net (code "68") (name "unconnected-(U6-Vcc-Pad3)") (class "Default")
      (node (ref "U6") (pin "3") (pinfunction "Vcc_3") (pintype "passive"))
    )
    (net (code "69") (name "unconnected-(U11-3V0-Pad2)") (class "Default")
      (node (ref "U11") (pin "2") (pinfunction "3V0_2") (pintype "passive+no_connect"))
    )
    (net (code "70") (name "unconnected-(U11-ADR-Pad7)") (class "Default")
      (node (ref "U11") (pin "7") (pinfunction "ADR_7") (pintype "passive+no_connect"))
    )
    (net (code "71") (name "unconnected-(U11-INT-Pad8)") (class "Default")
      (node (ref "U11") (pin "8") (pinfunction "INT_8") (pintype "passive+no_connect"))
    )
    (net (code "72") (name "unconnected-(U11-PS0-Pad10)") (class "Default")
      (node (ref "U11") (pin "10") (pinfunction "PS0_10") (pintype "passive+no_connect"))
    )
    (net (code "73") (name "unconnected-(U11-PS1-Pad9)") (class "Default")
      (node (ref "U11") (pin "9") (pinfunction "PS1_9") (pintype "passive+no_connect"))
    )
    (net (code "74") (name "unconnected-(U11-RST-Pad6)") (class "Default")
      (node (ref "U11") (pin "6") (pinfunction "RST_6") (pintype "passive+no_connect"))
    )
  )
)
